# Main.net
KiCad netlist of a schematic drawn in Altium Designer
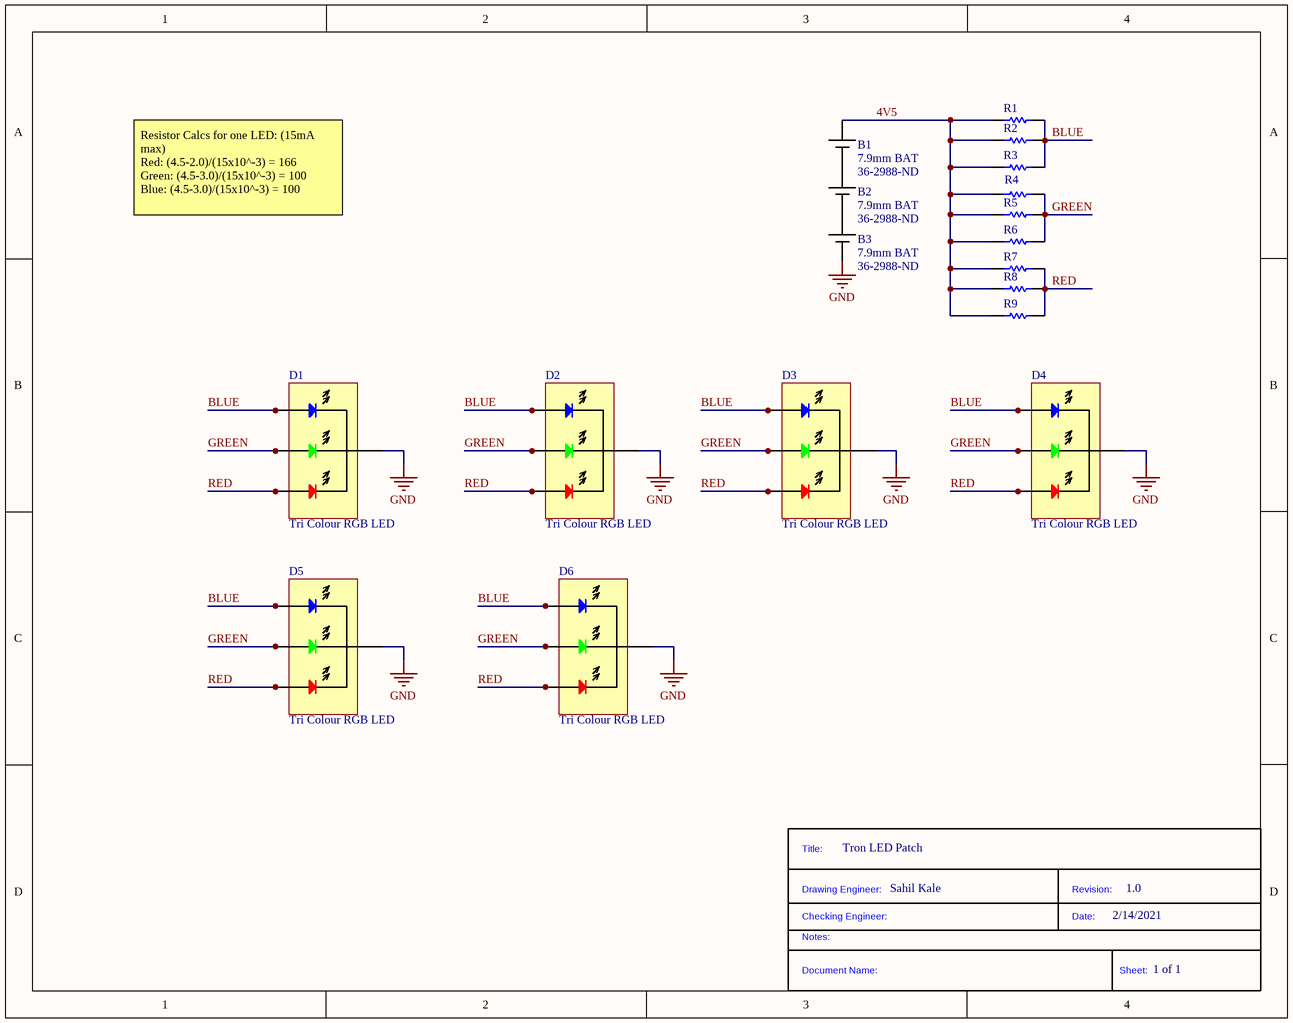
[diagram p0: Main.SchDoc]

(export (version "E")
  (design (tool "Eeschema 10.0.6"))
  (components
    (comp (ref "*")
      (value "TitleBlock")
      (description "Standard Title Block")
      (libsource (lib "SKALE_LIB") (part "TitleBlock"))
    )
    (comp (ref "B1")
      (value "7.9mm BAT")
      (footprint "2988")
      (description "KEYSTONE         2988            BATTERY CONTACT, 7.9MM HEAR AID CELL, SURFACE MT")
      (fields
        (field (name "MANUFACTURER") "Keystone Electronics")
        (field (name "MANUFACTURER PART NUMBER") "2988")
        (field (name "SUPPLIER PART NUMBER 1") "36-2988-ND")
      )
      (libsource (lib "SKALE_LIB") (part "CCELL HOLDER 7.9MM"))
    )
    (comp (ref "B2")
      (value "7.9mm BAT")
      (footprint "2988")
      (description "KEYSTONE         2988            BATTERY CONTACT, 7.9MM HEAR AID CELL, SURFACE MT")
      (fields
        (field (name "MANUFACTURER") "Keystone Electronics")
        (field (name "MANUFACTURER PART NUMBER") "2988")
        (field (name "SUPPLIER PART NUMBER 1") "36-2988-ND")
      )
      (libsource (lib "SKALE_LIB") (part "CCELL HOLDER 7.9MM"))
    )
    (comp (ref "B3")
      (value "7.9mm BAT")
      (footprint "2988")
      (description "KEYSTONE         2988            BATTERY CONTACT, 7.9MM HEAR AID CELL, SURFACE MT")
      (fields
        (field (name "MANUFACTURER") "Keystone Electronics")
        (field (name "MANUFACTURER PART NUMBER") "2988")
        (field (name "SUPPLIER PART NUMBER 1") "36-2988-ND")
      )
      (libsource (lib "SKALE_LIB") (part "CCELL HOLDER 7.9MM"))
    )
    (comp (ref "D1")
      (value "Tri Colour RGB LED")
      (footprint "RGB_LED_THRUHOLE")
      (libsource (lib "SKALE_LIB") (part "LED_RGB_THRUHOLE"))
    )
    (comp (ref "D2")
      (value "Tri Colour RGB LED")
      (footprint "RGB_LED_THRUHOLE")
      (libsource (lib "SKALE_LIB") (part "LED_RGB_THRUHOLE"))
    )
    (comp (ref "D3")
      (value "Tri Colour RGB LED")
      (footprint "RGB_LED_THRUHOLE")
      (libsource (lib "SKALE_LIB") (part "LED_RGB_THRUHOLE"))
    )
    (comp (ref "D4")
      (value "Tri Colour RGB LED")
      (footprint "RGB_LED_THRUHOLE")
      (libsource (lib "SKALE_LIB") (part "LED_RGB_THRUHOLE"))
    )
    (comp (ref "D5")
      (value "Tri Colour RGB LED")
      (footprint "RGB_LED_THRUHOLE")
      (libsource (lib "SKALE_LIB") (part "LED_RGB_THRUHOLE"))
    )
    (comp (ref "D6")
      (value "Tri Colour RGB LED")
      (footprint "RGB_LED_THRUHOLE")
      (libsource (lib "SKALE_LIB") (part "LED_RGB_THRUHOLE"))
    )
    (comp (ref "R1")
      (value "?Ω")
      (footprint "Generic ThroughHole")
      (description "Generic Through Hole Resistor")
      (libsource (lib "SKALE_LIB") (part "GENERIC - RES"))
    )
    (comp (ref "R2")
      (value "?Ω")
      (footprint "Generic ThroughHole")
      (description "Generic Through Hole Resistor")
      (libsource (lib "SKALE_LIB") (part "GENERIC - RES"))
    )
    (comp (ref "R3")
      (value "?Ω")
      (footprint "Generic ThroughHole")
      (description "Generic Through Hole Resistor")
      (libsource (lib "SKALE_LIB") (part "GENERIC - RES"))
    )
    (comp (ref "R4")
      (value "?Ω")
      (footprint "Generic ThroughHole")
      (description "Generic Through Hole Resistor")
      (libsource (lib "SKALE_LIB") (part "GENERIC - RES"))
    )
    (comp (ref "R5")
      (value "?Ω")
      (footprint "Generic ThroughHole")
      (description "Generic Through Hole Resistor")
      (libsource (lib "SKALE_LIB") (part "GENERIC - RES"))
    )
    (comp (ref "R6")
      (value "?Ω")
      (footprint "Generic ThroughHole")
      (description "Generic Through Hole Resistor")
      (libsource (lib "SKALE_LIB") (part "GENERIC - RES"))
    )
    (comp (ref "R7")
      (value "?Ω")
      (footprint "Generic ThroughHole")
      (description "Generic Through Hole Resistor")
      (libsource (lib "SKALE_LIB") (part "GENERIC - RES"))
    )
    (comp (ref "R8")
      (value "?Ω")
      (footprint "Generic ThroughHole")
      (description "Generic Through Hole Resistor")
      (libsource (lib "SKALE_LIB") (part "GENERIC - RES"))
    )
    (comp (ref "R9")
      (value "?Ω")
      (footprint "Generic ThroughHole")
      (description "Generic Through Hole Resistor")
      (libsource (lib "SKALE_LIB") (part "GENERIC - RES"))
    )
  )
  (nets
    (net (code "1") (name "/4V5") (class "Default")
      (node (ref "B1") (pin "2") (pinfunction "+_2") (pintype "passive"))
      (node (ref "R1") (pin "1") (pinfunction "1_1") (pintype "passive"))
      (node (ref "R2") (pin "1") (pinfunction "1_1") (pintype "passive"))
      (node (ref "R3") (pin "1") (pinfunction "1_1") (pintype "passive"))
      (node (ref "R4") (pin "1") (pinfunction "1_1") (pintype "passive"))
      (node (ref "R5") (pin "1") (pinfunction "1_1") (pintype "passive"))
      (node (ref "R6") (pin "1") (pinfunction "1_1") (pintype "passive"))
      (node (ref "R7") (pin "1") (pinfunction "1_1") (pintype "passive"))
      (node (ref "R8") (pin "1") (pinfunction "1_1") (pintype "passive"))
      (node (ref "R9") (pin "1") (pinfunction "1_1") (pintype "passive"))
    )
    (net (code "2") (name "/BLUE") (class "Default")
      (node (ref "D1") (pin "3") (pinfunction "Blue_+_3") (pintype "passive"))
      (node (ref "D1") (pin "6") (pinfunction "Blue_+_6") (pintype "passive"))
      (node (ref "D2") (pin "3") (pinfunction "Blue_+_3") (pintype "passive"))
      (node (ref "D2") (pin "6") (pinfunction "Blue_+_6") (pintype "passive"))
      (node (ref "D3") (pin "3") (pinfunction "Blue_+_3") (pintype "passive"))
      (node (ref "D3") (pin "6") (pinfunction "Blue_+_6") (pintype "passive"))
      (node (ref "D4") (pin "3") (pinfunction "Blue_+_3") (pintype "passive"))
      (node (ref "D4") (pin "6") (pinfunction "Blue_+_6") (pintype "passive"))
      (node (ref "D5") (pin "3") (pinfunction "Blue_+_3") (pintype "passive"))
      (node (ref "D5") (pin "6") (pinfunction "Blue_+_6") (pintype "passive"))
      (node (ref "D6") (pin "3") (pinfunction "Blue_+_3") (pintype "passive"))
      (node (ref "D6") (pin "6") (pinfunction "Blue_+_6") (pintype "passive"))
      (node (ref "R1") (pin "2") (pinfunction "2_2") (pintype "passive"))
      (node (ref "R2") (pin "2") (pinfunction "2_2") (pintype "passive"))
      (node (ref "R3") (pin "2") (pinfunction "2_2") (pintype "passive"))
    )
    (net (code "3") (name "/GREEN") (class "Default")
      (node (ref "D1") (pin "2") (pinfunction "Green_+_2") (pintype "passive"))
      (node (ref "D2") (pin "2") (pinfunction "Green_+_2") (pintype "passive"))
      (node (ref "D3") (pin "2") (pinfunction "Green_+_2") (pintype "passive"))
      (node (ref "D4") (pin "2") (pinfunction "Green_+_2") (pintype "passive"))
      (node (ref "D5") (pin "2") (pinfunction "Green_+_2") (pintype "passive"))
      (node (ref "D6") (pin "2") (pinfunction "Green_+_2") (pintype "passive"))
      (node (ref "R4") (pin "2") (pinfunction "2_2") (pintype "passive"))
      (node (ref "R5") (pin "2") (pinfunction "2_2") (pintype "passive"))
      (node (ref "R6") (pin "2") (pinfunction "2_2") (pintype "passive"))
    )
    (net (code "4") (name "/RED") (class "Default")
      (node (ref "D1") (pin "1") (pinfunction "Red_+_1") (pintype "passive"))
      (node (ref "D1") (pin "4") (pinfunction "Red_+_4") (pintype "passive"))
      (node (ref "D2") (pin "1") (pinfunction "Red_+_1") (pintype "passive"))
      (node (ref "D2") (pin "4") (pinfunction "Red_+_4") (pintype "passive"))
      (node (ref "D3") (pin "1") (pinfunction "Red_+_1") (pintype "passive"))
      (node (ref "D3") (pin "4") (pinfunction "Red_+_4") (pintype "passive"))
      (node (ref "D4") (pin "1") (pinfunction "Red_+_1") (pintype "passive"))
      (node (ref "D4") (pin "4") (pinfunction "Red_+_4") (pintype "passive"))
      (node (ref "D5") (pin "1") (pinfunction "Red_+_1") (pintype "passive"))
      (node (ref "D5") (pin "4") (pinfunction "Red_+_4") (pintype "passive"))
      (node (ref "D6") (pin "1") (pinfunction "Red_+_1") (pintype "passive"))
      (node (ref "D6") (pin "4") (pinfunction "Red_+_4") (pintype "passive"))
      (node (ref "R7") (pin "2") (pinfunction "2_2") (pintype "passive"))
      (node (ref "R8") (pin "2") (pinfunction "2_2") (pintype "passive"))
      (node (ref "R9") (pin "2") (pinfunction "2_2") (pintype "passive"))
    )
    (net (code "5") (name "GND") (class "Default")
      (node (ref "B3") (pin "1") (pinfunction "-_1") (pintype "passive"))
      (node (ref "D1") (pin "4") (pinfunction "GND_4") (pintype "passive"))
      (node (ref "D2") (pin "4") (pinfunction "GND_4") (pintype "passive"))
      (node (ref "D3") (pin "4") (pinfunction "GND_4") (pintype "passive"))
      (node (ref "D4") (pin "4") (pinfunction "GND_4") (pintype "passive"))
      (node (ref "D5") (pin "4") (pinfunction "GND_4") (pintype "passive"))
      (node (ref "D6") (pin "4") (pinfunction "GND_4") (pintype "passive"))
    )
    (net (code "6") (name "Net-(B1--)") (class "Default")
      (node (ref "B1") (pin "1") (pinfunction "-_1") (pintype "passive"))
      (node (ref "B2") (pin "2") (pinfunction "+_2") (pintype "passive"))
    )
    (net (code "7") (name "Net-(B2--)") (class "Default")
      (node (ref "B2") (pin "1") (pinfunction "-_1") (pintype "passive"))
      (node (ref "B3") (pin "2") (pinfunction "+_2") (pintype "passive"))
    )
  )
)
